# LEDs.net
KiCad netlist of a schematic drawn in Altium Designer
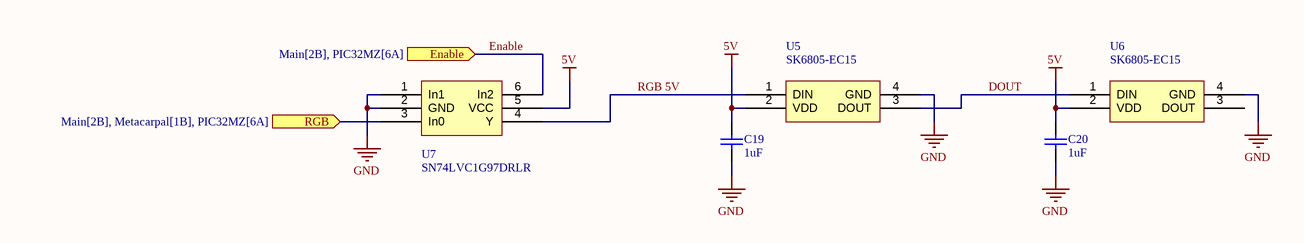
[diagram p0: LEDs.SchDoc]

(export (version "E")
  (design (tool "Eeschema 10.0.6"))
  (components
    (comp (ref "C19") (value "1uF") (footprint "Capacitor 0402") (libsource (lib "x-io") (part "Capacitor")))
    (comp (ref "C20") (value "1uF") (footprint "Capacitor 0402") (libsource (lib "x-io") (part "Capacitor")))
    (comp (ref "U5")
      (value "SK6805-EC15")
      (footprint "SK6805-EC15")
      (libsource (lib "x-io") (part "SK6805-EC15"))
    )
    (comp (ref "U6")
      (value "SK6805-EC15")
      (footprint "SK6805-EC15")
      (libsource (lib "x-io") (part "SK6805-EC15"))
    )
    (comp (ref "U7")
      (value "SN74LVC1G97DRLR")
      (footprint "SOT-666")
      (libsource (lib "x-io") (part "SN74LVC1G97DRLR"))
    )
  )
  (nets
    (net (code "1") (name "/DOUT") (class "Default")
      (node (ref "U5") (pin "3") (pinfunction "DOUT_3") (pintype "passive"))
      (node (ref "U6") (pin "1") (pinfunction "DIN_1") (pintype "passive"))
    )
    (net (code "2") (name "/Enable") (class "Default")
      (node (ref "U7") (pin "6") (pinfunction "In2_6") (pintype "passive"))
    )
    (net (code "3") (name "/RGB") (class "Default")
      (node (ref "U7") (pin "3") (pinfunction "In0_3") (pintype "passive"))
    )
    (net (code "4") (name "/RGB 5V") (class "Default")
      (node (ref "U5") (pin "1") (pinfunction "DIN_1") (pintype "passive"))
      (node (ref "U7") (pin "4") (pinfunction "Y_4") (pintype "passive"))
    )
    (net (code "5") (name "5V") (class "Default")
      (node (ref "C19") (pin "2") (pinfunction "2_2") (pintype "passive"))
      (node (ref "C20") (pin "2") (pinfunction "2_2") (pintype "passive"))
      (node (ref "U5") (pin "2") (pinfunction "VDD_2") (pintype "passive"))
      (node (ref "U6") (pin "2") (pinfunction "VDD_2") (pintype "passive"))
      (node (ref "U7") (pin "5") (pinfunction "VCC_5") (pintype "passive"))
    )
    (net (code "6") (name "GND") (class "Default")
      (node (ref "C19") (pin "1") (pinfunction "1_1") (pintype "passive"))
      (node (ref "C20") (pin "1") (pinfunction "1_1") (pintype "passive"))
      (node (ref "U5") (pin "4") (pinfunction "GND_4") (pintype "passive"))
      (node (ref "U6") (pin "4") (pinfunction "GND_4") (pintype "passive"))
      (node (ref "U7") (pin "1") (pinfunction "In1_1") (pintype "passive"))
      (node (ref "U7") (pin "2") (pinfunction "GND_2") (pintype "passive"))
    )
    (net (code "7") (name "unconnected-(U6-DOUT-Pad3)") (class "Default")
      (node (ref "U6") (pin "3") (pinfunction "DOUT_3") (pintype "passive"))
    )
  )
)
